# power_control_system.net
KiCad netlist of a schematic drawn in EAGLE
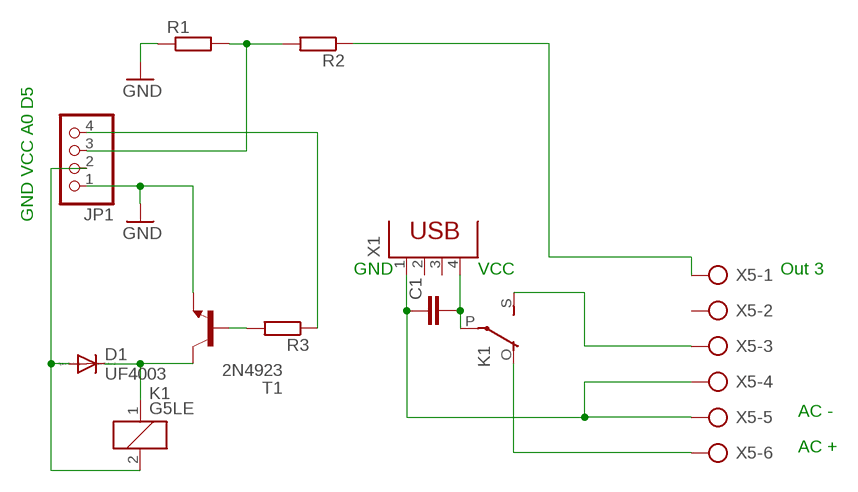
[diagram p0: schematic, sheet 1]

(export (version "E")
  (design (tool "Eeschema 10.0.6"))
  (components
    (comp (ref "C1")
      (value "C2,5-3")
      (footprint "eagle-import:C2.5-3")
      (libsource (lib "eagle-import") (part "C2,5-3"))
    )
    (comp (ref "D1")
      (value "UF4003")
      (footprint "eagle-import:DO41-10")
      (libsource (lib "eagle-import") (part "UF4003"))
    )
    (comp (ref "JP1")
      (value "PINHD-1X4")
      (footprint "eagle-import:1X04")
      (libsource (lib "eagle-import") (part "PINHD-1X4"))
    )
    (comp (ref "K1")
      (value "G5LE")
      (footprint "eagle-import:G5LE")
      (libsource (lib "eagle-import") (part "G5LE"))
    )
    (comp (ref "R1")
      (value "R-EU_0204/2V")
      (footprint "eagle-import:0204V")
      (libsource (lib "eagle-import") (part "R-EU_0204/2V"))
    )
    (comp (ref "R2")
      (value "R-EU_0204/2V")
      (footprint "eagle-import:0204V")
      (libsource (lib "eagle-import") (part "R-EU_0204/2V"))
    )
    (comp (ref "R3")
      (value "R-EU_0204/2V")
      (footprint "eagle-import:0204V")
      (libsource (lib "eagle-import") (part "R-EU_0204/2V"))
    )
    (comp (ref "T1")
      (value "2N4923")
      (footprint "eagle-import:TO126")
      (libsource (lib "eagle-import") (part "2N4923"))
    )
    (comp (ref "X1")
      (value "PN87520")
      (footprint "eagle-import:PN87520")
      (libsource (lib "eagle-import") (part "PN87520"))
    )
    (comp (ref "X5")
      (value "AK300/6")
      (footprint "eagle-import:AK300_6")
      (libsource (lib "eagle-import") (part "AK300/6"))
    )
  )
  (nets
    (net (code "1") (name "GND") (class "Default")
      (node (ref "JP1") (pin "1") (pinfunction "1_1") (pintype "passive"))
      (node (ref "R1") (pin "1") (pinfunction "1_1") (pintype "passive"))
      (node (ref "T1") (pin "1") (pinfunction "E_1") (pintype "passive"))
    )
    (net (code "2") (name "Net-(C1-Pad2)") (class "Default")
      (node (ref "C1") (pin "2") (pinfunction "2_2") (pintype "passive"))
      (node (ref "K1") (pin "P") (pinfunction "P_P") (pintype "passive"))
      (node (ref "X1") (pin "4") (pinfunction "4_4") (pintype "passive"))
    )
    (net (code "3") (name "Net-(D1-PadA)") (class "Default")
      (node (ref "D1") (pin "A") (pinfunction "A_A") (pintype "passive"))
      (node (ref "JP1") (pin "2") (pinfunction "2_2") (pintype "passive"))
      (node (ref "K1") (pin "2") (pinfunction "2_2") (pintype "passive"))
    )
    (net (code "4") (name "Net-(JP1-Pad3)") (class "Default")
      (node (ref "JP1") (pin "3") (pinfunction "3_3") (pintype "passive"))
      (node (ref "R1") (pin "2") (pinfunction "2_2") (pintype "passive"))
      (node (ref "R2") (pin "2") (pinfunction "2_2") (pintype "passive"))
    )
    (net (code "5") (name "Net-(JP1-Pad4)") (class "Default")
      (node (ref "JP1") (pin "4") (pinfunction "4_4") (pintype "passive"))
      (node (ref "R3") (pin "1") (pinfunction "1_1") (pintype "passive"))
    )
    (net (code "6") (name "Net-(T1-B)") (class "Default")
      (node (ref "R3") (pin "2") (pinfunction "2_2") (pintype "passive"))
      (node (ref "T1") (pin "3") (pinfunction "B_3") (pintype "passive"))
    )
    (net (code "7") (name "Net-(T1-C)") (class "Default")
      (node (ref "D1") (pin "C") (pinfunction "C_C") (pintype "passive"))
      (node (ref "K1") (pin "1") (pinfunction "1_1") (pintype "passive"))
      (node (ref "T1") (pin "2") (pinfunction "C_2") (pintype "passive"))
    )
    (net (code "8") (name "Net-(X5A-KL)") (class "Default")
      (node (ref "R2") (pin "1") (pinfunction "1_1") (pintype "passive"))
      (node (ref "X5") (pin "1") (pinfunction "KL_1") (pintype "passive"))
    )
    (net (code "9") (name "Net-(X5C-KL)") (class "Default")
      (node (ref "K1") (pin "S") (pinfunction "S_S") (pintype "passive"))
      (node (ref "X5") (pin "3") (pinfunction "KL_3") (pintype "passive"))
    )
    (net (code "10") (name "Net-(X5D-KL)") (class "Default")
      (node (ref "C1") (pin "1") (pinfunction "1_1") (pintype "passive"))
      (node (ref "X1") (pin "1") (pinfunction "1_1") (pintype "passive"))
      (node (ref "X5") (pin "4") (pinfunction "KL_4") (pintype "passive"))
      (node (ref "X5") (pin "5") (pinfunction "KL_5") (pintype "passive"))
    )
    (net (code "11") (name "Net-(X5F-KL)") (class "Default")
      (node (ref "K1") (pin "O") (pinfunction "O_O") (pintype "passive"))
      (node (ref "X5") (pin "6") (pinfunction "KL_6") (pintype "passive"))
    )
    (net (code "12") (name "unconnected-(X1-Pad2)") (class "Default")
      (node (ref "X1") (pin "2") (pinfunction "2_2") (pintype "passive"))
    )
    (net (code "13") (name "unconnected-(X1-Pad3)") (class "Default")
      (node (ref "X1") (pin "3") (pinfunction "3_3") (pintype "passive"))
    )
    (net (code "14") (name "unconnected-(X5B-KL-Pad2)") (class "Default")
      (node (ref "X5") (pin "2") (pinfunction "KL_2") (pintype "passive"))
    )
  )
)
